# candy.net
KiCad netlist of a schematic drawn in EAGLE
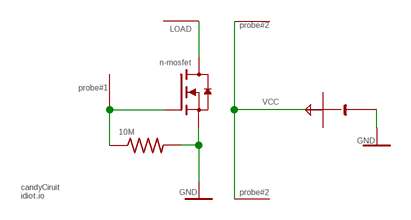
[diagram p0: schematic, sheet 1]

(export (version "E")
  (design (tool "Eeschema 10.0.6"))
  (components
    (comp (ref "10M")
      (value "R-US_R1206")
      (footprint "eagle-import:R1206")
      (libsource (lib "eagle-import") (part "R-US_R1206"))
    )
    (comp (ref "N-MOSFET")
      (value "n-mosfet")
      (footprint "eagle-import:SOT323")
      (libsource (lib "eagle-import") (part "N-MOSFETREGULAR"))
    )
    (comp (ref "U$1")
      (value "SMDPAD")
      (footprint "eagle-import:PADSMD")
      (libsource (lib "eagle-import") (part "SMDPAD"))
    )
    (comp (ref "U$4")
      (value "SMDPAD")
      (footprint "eagle-import:PADSMD")
      (libsource (lib "eagle-import") (part "SMDPAD"))
    )
    (comp (ref "U$5")
      (value "SMDPAD")
      (footprint "eagle-import:PADSMD")
      (libsource (lib "eagle-import") (part "SMDPAD"))
    )
    (comp (ref "U$7")
      (value "CR2032LINX")
      (footprint "eagle-import:CR2032-LINX")
      (libsource (lib "eagle-import") (part "CR2032LINX"))
    )
    (comp (ref "VCC")
      (value "SMDPAD")
      (footprint "eagle-import:PADSMD")
      (libsource (lib "eagle-import") (part "SMDPAD"))
    )
  )
  (nets
    (net (code "1") (name "/LOAD") (class "Default")
      (node (ref "N-MOSFET") (pin "3D") (pinfunction "D_3D") (pintype "passive"))
      (node (ref "U$4") (pin "P$1") (pinfunction "P$1_P$1") (pintype "bidirectional"))
    )
    (net (code "2") (name "/VCC") (class "Default")
      (node (ref "U$5") (pin "P$1") (pinfunction "P$1_P$1") (pintype "bidirectional"))
      (node (ref "U$7") (pin "+") (pinfunction "+_+") (pintype "passive"))
      (node (ref "U$7") (pin "+2") (pinfunction "+_+2") (pintype "passive"))
      (node (ref "VCC") (pin "P$1") (pinfunction "P$1_P$1") (pintype "bidirectional"))
    )
    (net (code "3") (name "GND") (class "Default")
      (node (ref "10M") (pin "2") (pinfunction "2_2") (pintype "passive"))
      (node (ref "N-MOSFET") (pin "2S") (pinfunction "S_2S") (pintype "passive"))
      (node (ref "U$7") (pin "-") (pinfunction "-_-") (pintype "passive"))
    )
    (net (code "4") (name "Net-(N-MOSFET-G)") (class "Default")
      (node (ref "10M") (pin "1") (pinfunction "1_1") (pintype "passive"))
      (node (ref "N-MOSFET") (pin "1G") (pinfunction "G_1G") (pintype "passive"))
      (node (ref "U$1") (pin "P$1") (pinfunction "P$1_P$1") (pintype "bidirectional"))
    )
  )
)
